# P09_Ethernet.net
KiCad netlist of a schematic drawn in Altium Designer
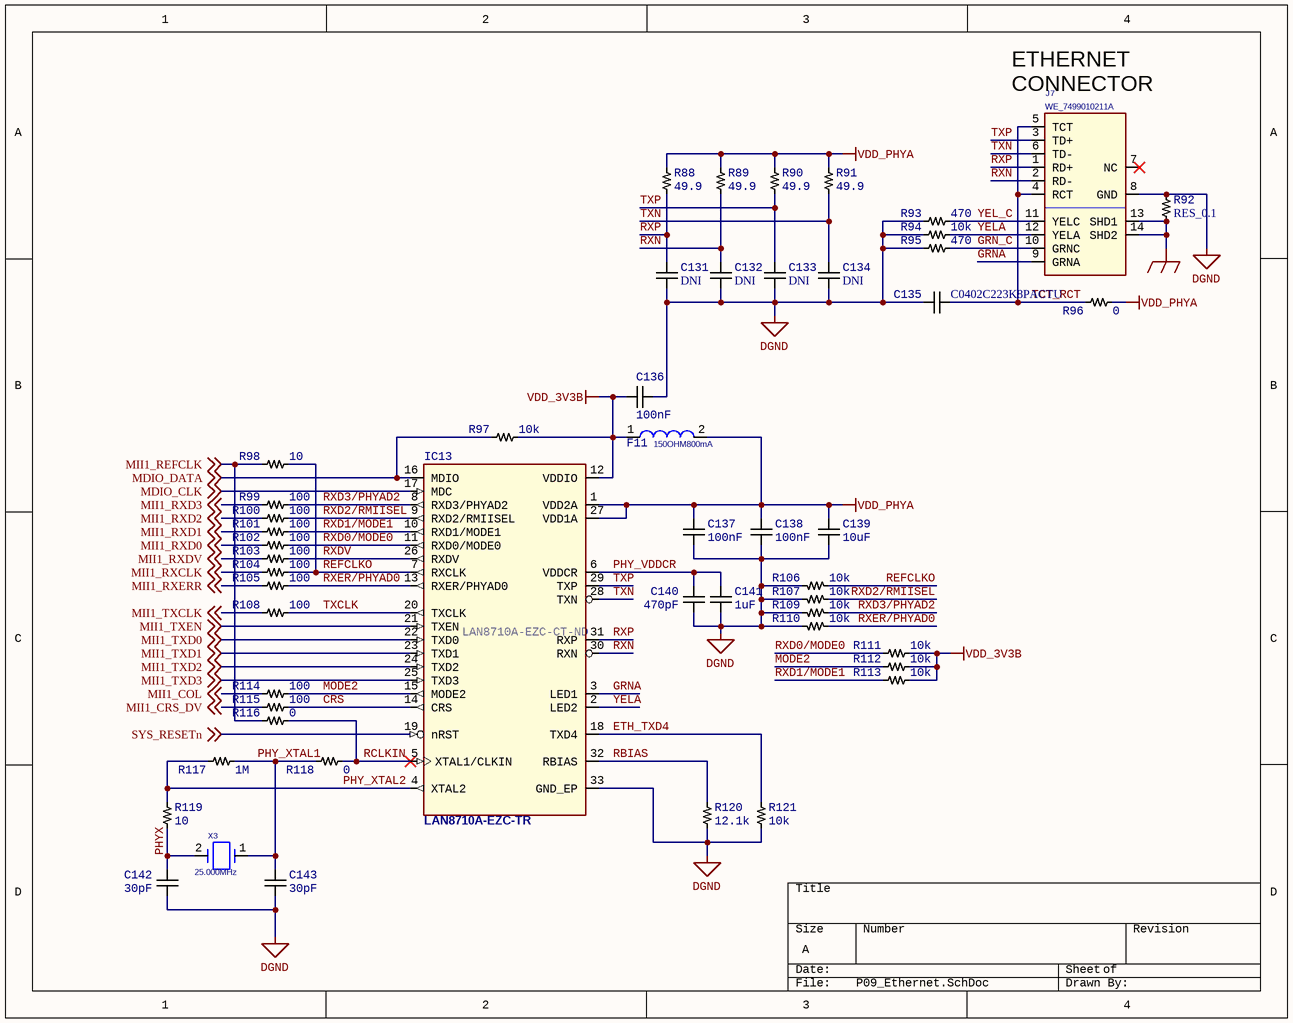
[diagram p0: P09_Ethernet.SchDoc]

(export (version "E")
  (design (tool "Eeschema 10.0.6"))
  (components
    (comp (ref "C131")
      (value "DNI")
      (footprint "Orient:CAP0402_DNI")
      (description "No insert capacitor")
      (libsource (lib "Orient") (part "CAP_15pF_DNI"))
    )
    (comp (ref "C132")
      (value "DNI")
      (footprint "Orient:CAP0402_DNI")
      (description "No insert capacitor")
      (libsource (lib "Orient") (part "CAP_15pF_DNI"))
    )
    (comp (ref "C133")
      (value "DNI")
      (footprint "Orient:CAP0402_DNI")
      (description "No insert capacitor")
      (libsource (lib "Orient") (part "CAP_15pF_DNI"))
    )
    (comp (ref "C134")
      (value "DNI")
      (footprint "Orient:CAP0402_DNI")
      (description "No insert capacitor")
      (libsource (lib "Orient") (part "CAP_15pF_DNI"))
    )
    (comp (ref "C135")
      (value "C0402C223K8PACTU")
      (footprint "Orient:CAP0402")
      (description "MLCC 22nF 0402 SMD")
      (fields (field (name "MANUFACTURER") "KEMET") (field (name "TOLERANCE") "10%"))
      (libsource (lib "Orient") (part "CAP_22nF"))
    )
    (comp (ref "C136")
      (value "C0402C104K4RACTU")
      (footprint "Orient:CAP0402")
      (description "MLCC 100nF 0402 SMD")
      (fields
        (field (name "MANUFACTURER") "KEMET")
        (field (name "CAPACITANCE") "100nF")
        (field (name "TOLERANCE") "10%")
      )
      (libsource (lib "Orient") (part "CAP_100nF"))
    )
    (comp (ref "C137")
      (value "C0402C104K4RACTU")
      (footprint "Orient:CAP0402")
      (description "MLCC 100nF 0402 SMD")
      (fields
        (field (name "MANUFACTURER") "KEMET")
        (field (name "CAPACITANCE") "100nF")
        (field (name "TOLERANCE") "10%")
      )
      (libsource (lib "Orient") (part "CAP_100nF"))
    )
    (comp (ref "C138")
      (value "C0402C104K4RACTU")
      (footprint "Orient:CAP0402")
      (description "MLCC 100nF 0402 SMD")
      (fields
        (field (name "MANUFACTURER") "KEMET")
        (field (name "CAPACITANCE") "100nF")
        (field (name "TOLERANCE") "10%")
      )
      (libsource (lib "Orient") (part "CAP_100nF"))
    )
    (comp (ref "C139")
      (value "10uF")
      (footprint "Orient:CAP0805")
      (description "MLCC 10uF 0805 SMD")
      (fields
        (field (name "MANUFACTURER") "TDK")
        (field (name "MANUFACTURER PART NUMBER") "C2012X6S1A106K085AC")
      )
      (libsource (lib "Orient") (part "CAP_10uF"))
    )
    (comp (ref "C140")
      (value "470pF")
      (footprint "Orient:CAP0402")
      (description "MLCC 470pF 0402 SMD")
      (fields
        (field (name "MANUFACTURER") "Murata")
        (field (name "MANUFACTURER PART NUMBER") "GRM155R71H471KA01D")
      )
      (libsource (lib "Orient") (part "CAP_470pF"))
    )
    (comp (ref "C141")
      (value "1uF")
      (footprint "Orient:CAP0402")
      (description "MLCC 1uF 0402 SMD")
      (fields
        (field (name "MANUFACTURER") "Yageo")
        (field (name "MANUFACTURER PART NUMBER") "CC0402KRX5R6BB105")
      )
      (libsource (lib "Orient") (part "CAP_1uF"))
    )
    (comp (ref "C142")
      (value "CC0402JRNPO9BN300")
      (footprint "Orient:CAP0402")
      (description "MLCC 30pF 0402 SMD")
      (fields
        (field (name "MANUFACTURER") "Yageo")
        (field (name "TOLERANCE") "5%")
        (field (name "CAPACITANCE") "30pF")
      )
      (libsource (lib "Orient") (part "CAP_30pF"))
    )
    (comp (ref "C143")
      (value "CC0402JRNPO9BN300")
      (footprint "Orient:CAP0402")
      (description "MLCC 30pF 0402 SMD")
      (fields
        (field (name "MANUFACTURER") "Yageo")
        (field (name "TOLERANCE") "5%")
        (field (name "CAPACITANCE") "30pF")
      )
      (libsource (lib "Orient") (part "CAP_30pF"))
    )
    (comp (ref "F11")
      (value "150OHM800mA")
      (footprint "Orient:FB0805")
      (description "FERRITE 800MA 150 OHM 0805 SMD")
      (fields (field (name "MFR") "Steward") (field (name "TIINTPARTNUMBER") "1L0010"))
      (libsource (lib "Orient") (part "FERR"))
    )
    (comp (ref "IC13")
      (value "LAN8710A-EZC-TR")
      (footprint "Orient:QFN-32")
      (description "Ethernet ICs 10/100 Ethernet XCVR w/HPAutoMDIX FlexPwr")
      (fields
        (field (name "PART#") "SMSC LAN8710A-EZK")
        (field (name "MANUFACTURER") "Microchip Technology")
        (field (name "SUPPLIER PART NUMBER 2") "LAN8710A-EZC-CT-ND")
      )
      (libsource (lib "Orient") (part "IC_Ethernet_XCVR"))
    )
    (comp (ref "J7")
      (value "WE_7499010211A")
      (description "WE-RJ45 LAN Transformer")
      (libsource (lib "Orient") (part "CONN_RJ45_MAG_WE_0"))
    )
    (comp (ref "R88")
      (value "RC0402FR-0749R9")
      (footprint "Orient:RES0402")
      (description "Resistor 49.9Ohm 0402 SMD")
      (fields
        (field (name "MANUFACTURER") "Yageo")
        (field (name "MANUFACTURER PART NUMBER") "RC0402FR-0749R9L")
        (field (name "RESISTANCE") "49.9")
      )
      (libsource (lib "Orient") (part "RES_49.9"))
    )
    (comp (ref "R89")
      (value "RC0402FR-0749R9")
      (footprint "Orient:RES0402")
      (description "Resistor 49.9Ohm 0402 SMD")
      (fields
        (field (name "MANUFACTURER") "Yageo")
        (field (name "MANUFACTURER PART NUMBER") "RC0402FR-0749R9L")
        (field (name "RESISTANCE") "49.9")
      )
      (libsource (lib "Orient") (part "RES_49.9"))
    )
    (comp (ref "R90")
      (value "RC0402FR-0749R9")
      (footprint "Orient:RES0402")
      (description "Resistor 49.9Ohm 0402 SMD")
      (fields
        (field (name "MANUFACTURER") "Yageo")
        (field (name "MANUFACTURER PART NUMBER") "RC0402FR-0749R9L")
        (field (name "RESISTANCE") "49.9")
      )
      (libsource (lib "Orient") (part "RES_49.9"))
    )
    (comp (ref "R91")
      (value "RC0402FR-0749R9")
      (footprint "Orient:RES0402")
      (description "Resistor 49.9Ohm 0402 SMD")
      (fields
        (field (name "MANUFACTURER") "Yageo")
        (field (name "MANUFACTURER PART NUMBER") "RC0402FR-0749R9L")
        (field (name "RESISTANCE") "49.9")
      )
      (libsource (lib "Orient") (part "RES_49.9"))
    )
    (comp (ref "R92")
      (value "RES_0.1")
      (description "Resistor 0.1Ohm 0805 SMD")
      (libsource (lib "Orient") (part "RES_0.1"))
    )
    (comp (ref "R93")
      (value "RC0402FR-07470RL")
      (footprint "Orient:RES0402")
      (description "Resistor 470Ohm 0402 SMD")
      (fields
        (field (name "MANUFACTURER") "Yageo Phycomp")
        (field (name "TOLERANCE") "1%")
        (field (name "RESISTANCE") "470")
      )
      (libsource (lib "Orient") (part "RES_470"))
    )
    (comp (ref "R94")
      (value "RC0402FR-0710KL")
      (footprint "Orient:RES0402")
      (description "Resistor 10kOhm 0402 SMD")
      (fields
        (field (name "MANUFACTURER") "Yageo")
        (field (name "TOLERANCE") "1%")
        (field (name "RESISTANCE") "10k")
      )
      (libsource (lib "Orient") (part "RES_10k"))
    )
    (comp (ref "R95")
      (value "RC0402FR-07470RL")
      (footprint "Orient:RES0402")
      (description "Resistor 470Ohm 0402 SMD")
      (fields
        (field (name "MANUFACTURER") "Yageo Phycomp")
        (field (name "TOLERANCE") "1%")
        (field (name "RESISTANCE") "470")
      )
      (libsource (lib "Orient") (part "RES_470"))
    )
    (comp (ref "R96")
      (value "RC0402JR-070RL")
      (footprint "Orient:RES0402")
      (description "Resistor 0Ohm 0402 SMD")
      (fields
        (field (name "MANUFACTURER") "Yageo")
        (field (name "TOLERANCE") "5%")
        (field (name "RESISTANCE") "0")
      )
      (libsource (lib "Orient") (part "RES_0"))
    )
    (comp (ref "R97")
      (value "RC0402FR-0710KL")
      (footprint "Orient:RES0402")
      (description "Resistor 10kOhm 0402 SMD")
      (fields
        (field (name "MANUFACTURER") "Yageo")
        (field (name "TOLERANCE") "1%")
        (field (name "RESISTANCE") "10k")
      )
      (libsource (lib "Orient") (part "RES_10k"))
    )
    (comp (ref "R98")
      (value "RC0402FR-0710RL")
      (footprint "Orient:RES0402")
      (description "Resistor 10Ohm 0402 SMD")
      (fields
        (field (name "MANUFACTURER") "Yageo")
        (field (name "TOLERANCE") "1%")
        (field (name "RESISTANCE") "10")
      )
      (libsource (lib "Orient") (part "RES_10"))
    )
    (comp (ref "R99")
      (value "RC0402FR-07100RL")
      (footprint "Orient:RES0402")
      (description "Resistor 100Ohm 0402 SMD")
      (fields
        (field (name "MANUFACTURER") "Yageo")
        (field (name "TOLERANCE") "1%")
        (field (name "RESISTANCE") "100")
      )
      (libsource (lib "Orient") (part "RES_100"))
    )
    (comp (ref "R100")
      (value "RC0402FR-07100RL")
      (footprint "Orient:RES0402")
      (description "Resistor 100Ohm 0402 SMD")
      (fields
        (field (name "MANUFACTURER") "Yageo")
        (field (name "TOLERANCE") "1%")
        (field (name "RESISTANCE") "100")
      )
      (libsource (lib "Orient") (part "RES_100"))
    )
    (comp (ref "R101")
      (value "RC0402FR-07100RL")
      (footprint "Orient:RES0402")
      (description "Resistor 100Ohm 0402 SMD")
      (fields
        (field (name "MANUFACTURER") "Yageo")
        (field (name "TOLERANCE") "1%")
        (field (name "RESISTANCE") "100")
      )
      (libsource (lib "Orient") (part "RES_100"))
    )
    (comp (ref "R102")
      (value "RC0402FR-07100RL")
      (footprint "Orient:RES0402")
      (description "Resistor 100Ohm 0402 SMD")
      (fields
        (field (name "MANUFACTURER") "Yageo")
        (field (name "TOLERANCE") "1%")
        (field (name "RESISTANCE") "100")
      )
      (libsource (lib "Orient") (part "RES_100"))
    )
    (comp (ref "R103")
      (value "RC0402FR-07100RL")
      (footprint "Orient:RES0402")
      (description "Resistor 100Ohm 0402 SMD")
      (fields
        (field (name "MANUFACTURER") "Yageo")
        (field (name "TOLERANCE") "1%")
        (field (name "RESISTANCE") "100")
      )
      (libsource (lib "Orient") (part "RES_100"))
    )
    (comp (ref "R104")
      (value "RC0402FR-07100RL")
      (footprint "Orient:RES0402")
      (description "Resistor 100Ohm 0402 SMD")
      (fields
        (field (name "MANUFACTURER") "Yageo")
        (field (name "TOLERANCE") "1%")
        (field (name "RESISTANCE") "100")
      )
      (libsource (lib "Orient") (part "RES_100"))
    )
    (comp (ref "R105")
      (value "RC0402FR-07100RL")
      (footprint "Orient:RES0402")
      (description "Resistor 100Ohm 0402 SMD")
      (fields
        (field (name "MANUFACTURER") "Yageo")
        (field (name "TOLERANCE") "1%")
        (field (name "RESISTANCE") "100")
      )
      (libsource (lib "Orient") (part "RES_100"))
    )
    (comp (ref "R106")
      (value "RC0402FR-0710KL")
      (footprint "Orient:RES0402")
      (description "Resistor 10kOhm 0402 SMD")
      (fields
        (field (name "MANUFACTURER") "Yageo")
        (field (name "TOLERANCE") "1%")
        (field (name "RESISTANCE") "10k")
      )
      (libsource (lib "Orient") (part "RES_10k"))
    )
    (comp (ref "R107")
      (value "RC0402FR-0710KL")
      (footprint "Orient:RES0402")
      (description "Resistor 10kOhm 0402 SMD")
      (fields
        (field (name "MANUFACTURER") "Yageo")
        (field (name "TOLERANCE") "1%")
        (field (name "RESISTANCE") "10k")
      )
      (libsource (lib "Orient") (part "RES_10k"))
    )
    (comp (ref "R108")
      (value "RC0402FR-07100RL")
      (footprint "Orient:RES0402")
      (description "Resistor 100Ohm 0402 SMD")
      (fields
        (field (name "TOLERANCE") "1%")
        (field (name "MANUFACTURER") "Yageo")
        (field (name "RESISTANCE") "100")
      )
      (libsource (lib "Orient") (part "RES_100"))
    )
    (comp (ref "R109")
      (value "RC0402FR-0710KL")
      (footprint "Orient:RES0402")
      (description "Resistor 10kOhm 0402 SMD")
      (fields
        (field (name "MANUFACTURER") "Yageo")
        (field (name "TOLERANCE") "1%")
        (field (name "RESISTANCE") "10k")
      )
      (libsource (lib "Orient") (part "RES_10k"))
    )
    (comp (ref "R110")
      (value "RC0402FR-0710KL")
      (footprint "Orient:RES0402")
      (description "Resistor 10kOhm 0402 SMD")
      (fields
        (field (name "MANUFACTURER") "Yageo")
        (field (name "TOLERANCE") "1%")
        (field (name "RESISTANCE") "10k")
      )
      (libsource (lib "Orient") (part "RES_10k"))
    )
    (comp (ref "R111")
      (value "RC0402FR-0710KL")
      (footprint "Orient:RES0402")
      (description "Resistor 10kOhm 0402 SMD")
      (fields
        (field (name "MANUFACTURER") "Yageo")
        (field (name "TOLERANCE") "1%")
        (field (name "RESISTANCE") "10k")
      )
      (libsource (lib "Orient") (part "RES_10k"))
    )
    (comp (ref "R112")
      (value "RC0402FR-0710KL")
      (footprint "Orient:RES0402")
      (description "Resistor 10kOhm 0402 SMD")
      (fields
        (field (name "MANUFACTURER") "Yageo")
        (field (name "TOLERANCE") "1%")
        (field (name "RESISTANCE") "10k")
      )
      (libsource (lib "Orient") (part "RES_10k"))
    )
    (comp (ref "R113")
      (value "RC0402FR-0710KL")
      (footprint "Orient:RES0402")
      (description "Resistor 10kOhm 0402 SMD")
      (fields
        (field (name "MANUFACTURER") "Yageo")
        (field (name "TOLERANCE") "1%")
        (field (name "RESISTANCE") "10k")
      )
      (libsource (lib "Orient") (part "RES_10k"))
    )
    (comp (ref "R114")
      (value "RC0402FR-07100RL")
      (footprint "Orient:RES0402")
      (description "Resistor 100Ohm 0402 SMD")
      (fields
        (field (name "TOLERANCE") "1%")
        (field (name "MANUFACTURER") "Yageo")
        (field (name "RESISTANCE") "100")
      )
      (libsource (lib "Orient") (part "RES_100"))
    )
    (comp (ref "R115")
      (value "RC0402FR-07100RL")
      (footprint "Orient:RES0402")
      (description "Resistor 100Ohm 0402 SMD")
      (fields
        (field (name "MANUFACTURER") "Yageo")
        (field (name "TOLERANCE") "1%")
        (field (name "RESISTANCE") "100")
      )
      (libsource (lib "Orient") (part "RES_100"))
    )
    (comp (ref "R116")
      (value "RC0402JR-070RL")
      (footprint "Orient:RES0402")
      (description "Resistor 0Ohm 0402 SMD")
      (fields
        (field (name "MANUFACTURER") "Yageo")
        (field (name "TOLERANCE") "5%")
        (field (name "RESISTANCE") "0")
      )
      (libsource (lib "Orient") (part "RES_0"))
    )
    (comp (ref "R117")
      (value "RC0402FR-071ML")
      (footprint "Orient:RES0402")
      (description "Resistor 1MOhm 0402 SMD")
      (fields
        (field (name "MANUFACTURER") "Yageo")
        (field (name "TOLERANCE") "1%")
        (field (name "RESISTANCE") "1M")
      )
      (libsource (lib "Orient") (part "RES_1M"))
    )
    (comp (ref "R118")
      (value "RC0402JR-070RL")
      (footprint "Orient:RES0402")
      (description "Resistor 0Ohm 0402 SMD")
      (fields
        (field (name "MANUFACTURER") "Yageo")
        (field (name "TOLERANCE") "5%")
        (field (name "RESISTANCE") "0")
      )
      (libsource (lib "Orient") (part "RES_0"))
    )
    (comp (ref "R119")
      (value "RC0402FR-0710RL")
      (footprint "Orient:RES0402")
      (description "Resistor 10Ohm 0402 SMD")
      (fields
        (field (name "MANUFACTURER") "Yageo")
        (field (name "TOLERANCE") "1%")
        (field (name "RESISTANCE") "10")
      )
      (libsource (lib "Orient") (part "RES_10"))
    )
    (comp (ref "R120")
      (value "RC0402FR-0712K1L")
      (footprint "Orient:RES0402")
      (description "Resistor 12.1kOhm 0402 SMD")
      (fields
        (field (name "MANUFACTURER") "Yageo")
        (field (name "TOLERANCE") "1%")
        (field (name "RESISTANCE") "12.1k")
      )
      (libsource (lib "Orient") (part "RES_12.1k"))
    )
    (comp (ref "R121")
      (value "RC0402FR-0710KL")
      (footprint "Orient:RES0402")
      (description "Resistor 10kOhm 0402 SMD")
      (fields
        (field (name "MANUFACTURER") "Yageo")
        (field (name "TOLERANCE") "1%")
        (field (name "RESISTANCE") "10k")
      )
      (libsource (lib "Orient") (part "RES_10k"))
    )
    (comp (ref "X3")
      (value "25.000MHz")
      (footprint "Orient:XTAL150SMD_125X196")
      (fields
        (field (name "MANUFACTURER") "Abracon Corporation")
        (field (name "MANUFACTURER PART NUMBER") "ABM3-25.000MHZ-B2-T")
      )
      (libsource (lib "Orient") (part "Suntsu ITEMP 25MHz _0.005% 20pf"))
    )
  )
  (nets
    (net (code "1") (name "/CRS") (class "Default")
      (node (ref "IC13") (pin "14") (pinfunction "CRS_14") (pintype "output"))
      (node (ref "R115") (pin "1") (pintype "passive"))
    )
    (net (code "2") (name "/ETH_TXD4") (class "Default")
      (node (ref "IC13") (pin "18") (pinfunction "TXD4_18") (pintype "bidirectional"))
      (node (ref "R121") (pin "2") (pintype "passive"))
    )
    (net (code "3") (name "/GRNA") (class "Default")
      (node (ref "IC13") (pin "3") (pinfunction "LED1_3") (pintype "bidirectional"))
      (node (ref "J7") (pin "9") (pinfunction "GRNA_9") (pintype "passive"))
    )
    (net (code "4") (name "/GRN_C") (class "Default")
      (node (ref "J7") (pin "10") (pinfunction "GRNC_10") (pintype "passive"))
      (node (ref "R95") (pin "1") (pintype "passive"))
    )
    (net (code "5") (name "/MODE2") (class "Default")
      (node (ref "IC13") (pin "15") (pinfunction "MODE2_15") (pintype "output"))
      (node (ref "R112") (pin "1") (pintype "passive"))
      (node (ref "R114") (pin "1") (pintype "passive"))
    )
    (net (code "6") (name "/PHYX") (class "Default")
      (node (ref "C142") (pin "1") (pintype "passive"))
      (node (ref "R119") (pin "1") (pintype "passive"))
      (node (ref "X3") (pin "2") (pinfunction "2_2") (pintype "passive"))
    )
    (net (code "7") (name "/PHY_VDDCR") (class "Default")
      (node (ref "C140") (pin "1") (pintype "passive"))
      (node (ref "C141") (pin "1") (pintype "passive"))
      (node (ref "IC13") (pin "6") (pinfunction "VDDCR_6") (pintype "power_in"))
    )
    (net (code "8") (name "/PHY_XTAL1") (class "Default")
      (node (ref "C143") (pin "1") (pintype "passive"))
      (node (ref "R117") (pin "1") (pintype "passive"))
      (node (ref "R118") (pin "2") (pintype "passive"))
      (node (ref "X3") (pin "1") (pinfunction "1_1") (pintype "passive"))
    )
    (net (code "9") (name "/PHY_XTAL2") (class "Default")
      (node (ref "IC13") (pin "4") (pinfunction "XTAL2_4") (pintype "output"))
      (node (ref "R117") (pin "2") (pintype "passive"))
      (node (ref "R119") (pin "2") (pintype "passive"))
    )
    (net (code "10") (name "/RBIAS") (class "Default")
      (node (ref "IC13") (pin "32") (pinfunction "RBIAS_32") (pintype "passive"))
      (node (ref "R120") (pin "2") (pintype "passive"))
    )
    (net (code "11") (name "/RCLKIN") (class "Default")
      (node (ref "IC13") (pin "5") (pinfunction "XTAL1/CLKIN_5") (pintype "input"))
      (node (ref "R116") (pin "1") (pintype "passive"))
      (node (ref "R118") (pin "1") (pintype "passive"))
    )
    (net (code "12") (name "/REFCLKO") (class "Default")
      (node (ref "IC13") (pin "7") (pinfunction "RXCLK_7") (pintype "output"))
      (node (ref "R104") (pin "1") (pintype "passive"))
      (node (ref "R106") (pin "1") (pintype "passive"))
      (node (ref "R98") (pin "1") (pintype "passive"))
    )
    (net (code "13") (name "/RXD0{slash}MODE0") (class "Default")
      (node (ref "IC13") (pin "11") (pinfunction "RXD0/MODE0_11") (pintype "output"))
      (node (ref "R102") (pin "1") (pintype "passive"))
      (node (ref "R111") (pin "1") (pintype "passive"))
    )
    (net (code "14") (name "/RXD1{slash}MODE1") (class "Default")
      (node (ref "IC13") (pin "10") (pinfunction "RXD1/MODE1_10") (pintype "output"))
      (node (ref "R101") (pin "1") (pintype "passive"))
      (node (ref "R113") (pin "1") (pintype "passive"))
    )
    (net (code "15") (name "/RXD2{slash}RMIISEL") (class "Default")
      (node (ref "IC13") (pin "9") (pinfunction "RXD2/RMIISEL_9") (pintype "output"))
      (node (ref "R100") (pin "1") (pintype "passive"))
      (node (ref "R107") (pin "1") (pintype "passive"))
    )
    (net (code "16") (name "/RXD3{slash}PHYAD2") (class "Default")
      (node (ref "IC13") (pin "8") (pinfunction "RXD3/PHYAD2_8") (pintype "output"))
      (node (ref "R109") (pin "1") (pintype "passive"))
      (node (ref "R99") (pin "1") (pintype "passive"))
    )
    (net (code "17") (name "/RXDV") (class "Default")
      (node (ref "IC13") (pin "26") (pinfunction "RXDV_26") (pintype "output"))
      (node (ref "R103") (pin "1") (pintype "passive"))
    )
    (net (code "18") (name "/RXER{slash}PHYAD0") (class "Default")
      (node (ref "IC13") (pin "13") (pinfunction "RXER/PHYAD0_13") (pintype "output"))
      (node (ref "R105") (pin "1") (pintype "passive"))
      (node (ref "R110") (pin "1") (pintype "passive"))
    )
    (net (code "19") (name "/RXN") (class "Default")
      (node (ref "C132") (pin "1") (pintype "passive"))
      (node (ref "IC13") (pin "30") (pinfunction "RXN_30") (pintype "bidirectional"))
      (node (ref "J7") (pin "2") (pinfunction "RD-_2") (pintype "passive"))
      (node (ref "R89") (pin "2") (pintype "passive"))
    )
    (net (code "20") (name "/RXP") (class "Default")
      (node (ref "C131") (pin "1") (pintype "passive"))
      (node (ref "IC13") (pin "31") (pinfunction "RXP_31") (pintype "bidirectional"))
      (node (ref "J7") (pin "1") (pinfunction "RD+_1") (pintype "passive"))
      (node (ref "R88") (pin "2") (pintype "passive"))
    )
    (net (code "21") (name "/TCT_RCT") (class "Default")
      (node (ref "C135") (pin "2") (pintype "passive"))
      (node (ref "J7") (pin "4") (pinfunction "RCT_4") (pintype "passive"))
      (node (ref "J7") (pin "5") (pinfunction "TCT_5") (pintype "passive"))
      (node (ref "R96") (pin "2") (pintype "passive"))
    )
    (net (code "22") (name "/TXCLK") (class "Default")
      (node (ref "IC13") (pin "20") (pinfunction "TXCLK_20") (pintype "output"))
      (node (ref "R108") (pin "1") (pintype "passive"))
    )
    (net (code "23") (name "/TXN") (class "Default")
      (node (ref "C134") (pin "1") (pintype "passive"))
      (node (ref "IC13") (pin "28") (pinfunction "TXN_28") (pintype "bidirectional"))
      (node (ref "J7") (pin "6") (pinfunction "TD-_6") (pintype "passive"))
      (node (ref "R91") (pin "2") (pintype "passive"))
    )
    (net (code "24") (name "/TXP") (class "Default")
      (node (ref "C133") (pin "1") (pintype "passive"))
      (node (ref "IC13") (pin "29") (pinfunction "TXP_29") (pintype "bidirectional"))
      (node (ref "J7") (pin "3") (pinfunction "TD+_3") (pintype "passive"))
      (node (ref "R90") (pin "2") (pintype "passive"))
    )
    (net (code "25") (name "/YELA") (class "Default")
      (node (ref "IC13") (pin "2") (pinfunction "LED2_2") (pintype "bidirectional"))
      (node (ref "J7") (pin "12") (pinfunction "YELA_12") (pintype "passive"))
      (node (ref "R94") (pin "1") (pintype "passive"))
    )
    (net (code "26") (name "/YEL_C") (class "Default")
      (node (ref "J7") (pin "11") (pinfunction "YELC_11") (pintype "passive"))
      (node (ref "R93") (pin "1") (pintype "passive"))
    )
    (net (code "27") (name "DGND") (class "Default")
      (node (ref "C131") (pin "2") (pintype "passive"))
      (node (ref "C132") (pin "2") (pintype "passive"))
      (node (ref "C133") (pin "2") (pintype "passive"))
      (node (ref "C134") (pin "2") (pintype "passive"))
      (node (ref "C135") (pin "1") (pintype "passive"))
      (node (ref "C136") (pin "2") (pintype "passive"))
      (node (ref "C137") (pin "2") (pintype "passive"))
      (node (ref "C138") (pin "2") (pintype "passive"))
      (node (ref "C139") (pin "1") (pintype "passive"))
      (node (ref "C140") (pin "2") (pintype "passive"))
      (node (ref "C141") (pin "2") (pintype "passive"))
      (node (ref "C142") (pin "2") (pintype "passive"))
      (node (ref "C143") (pin "2") (pintype "passive"))
      (node (ref "IC13") (pin "33") (pinfunction "GND_EP_33") (pintype "power_in"))
      (node (ref "J7") (pin "8") (pinfunction "GND_8") (pintype "passive"))
      (node (ref "R106") (pin "2") (pintype "passive"))
      (node (ref "R107") (pin "2") (pintype "passive"))
      (node (ref "R109") (pin "2") (pintype "passive"))
      (node (ref "R110") (pin "2") (pintype "passive"))
      (node (ref "R120") (pin "1") (pintype "passive"))
      (node (ref "R121") (pin "1") (pintype "passive"))
      (node (ref "R92") (pin "2") (pintype "passive"))
      (node (ref "R93") (pin "2") (pintype "passive"))
      (node (ref "R94") (pin "2") (pintype "passive"))
      (node (ref "R95") (pin "2") (pintype "passive"))
    )
    (net (code "28") (name "GND_EARTH") (class "Default")
      (node (ref "J7") (pin "13") (pinfunction "SHD1_13") (pintype "passive"))
      (node (ref "J7") (pin "14") (pinfunction "SHD2_14") (pintype "passive"))
      (node (ref "R92") (pin "1") (pintype "passive"))
    )
    (net (code "29") (name "MDIO_CLK") (class "Default")
      (node (ref "IC13") (pin "17") (pinfunction "MDC_17") (pintype "input"))
    )
    (net (code "30") (name "MDIO_DATA") (class "Default")
      (node (ref "IC13") (pin "16") (pinfunction "MDIO_16") (pintype "bidirectional"))
      (node (ref "R97") (pin "2") (pintype "passive"))
    )
    (net (code "31") (name "MII1_COL") (class "Default") (node (ref "R114") (pin "2") (pintype "passive")))
    (net (code "32") (name "MII1_CRS_DV") (class "Default") (node (ref "R115") (pin "2") (pintype "passive")))
    (net (code "33") (name "MII1_REFCLK") (class "Default")
      (node (ref "R116") (pin "2") (pintype "passive"))
      (node (ref "R98") (pin "2") (pintype "passive"))
    )
    (net (code "34") (name "MII1_RXCLK") (class "Default") (node (ref "R104") (pin "2") (pintype "passive")))
    (net (code "35") (name "MII1_RXD0") (class "Default") (node (ref "R102") (pin "2") (pintype "passive")))
    (net (code "36") (name "MII1_RXD1") (class "Default") (node (ref "R101") (pin "2") (pintype "passive")))
    (net (code "37") (name "MII1_RXD2") (class "Default") (node (ref "R100") (pin "2") (pintype "passive")))
    (net (code "38") (name "MII1_RXD3") (class "Default") (node (ref "R99") (pin "2") (pintype "passive")))
    (net (code "39") (name "MII1_RXDV") (class "Default") (node (ref "R103") (pin "2") (pintype "passive")))
    (net (code "40") (name "MII1_RXERR") (class "Default") (node (ref "R105") (pin "2") (pintype "passive")))
    (net (code "41") (name "MII1_TXCLK") (class "Default") (node (ref "R108") (pin "2") (pintype "passive")))
    (net (code "42") (name "MII1_TXD0") (class "Default")
      (node (ref "IC13") (pin "22") (pinfunction "TXD0_22") (pintype "input"))
    )
    (net (code "43") (name "MII1_TXD1") (class "Default")
      (node (ref "IC13") (pin "23") (pinfunction "TXD1_23") (pintype "input"))
    )
    (net (code "44") (name "MII1_TXD2") (class "Default")
      (node (ref "IC13") (pin "24") (pinfunction "TXD2_24") (pintype "input"))
    )
    (net (code "45") (name "MII1_TXD3") (class "Default")
      (node (ref "IC13") (pin "25") (pinfunction "TXD3_25") (pintype "input"))
    )
    (net (code "46") (name "MII1_TXEN") (class "Default")
      (node (ref "IC13") (pin "21") (pinfunction "TXEN_21") (pintype "input"))
    )
    (net (code "47") (name "SYS_RESETn") (class "Default")
      (node (ref "IC13") (pin "19") (pinfunction "nRST_19") (pintype "input"))
    )
    (net (code "48") (name "VDD_3V3B") (class "Default")
      (node (ref "C136") (pin "1") (pintype "passive"))
      (node (ref "F11") (pin "1") (pinfunction "1_1") (pintype "passive"))
      (node (ref "IC13") (pin "12") (pinfunction "VDDIO_12") (pintype "power_in"))
      (node (ref "R111") (pin "2") (pintype "passive"))
      (node (ref "R112") (pin "2") (pintype "passive"))
      (node (ref "R113") (pin "2") (pintype "passive"))
      (node (ref "R97") (pin "1") (pintype "passive"))
    )
    (net (code "49") (name "VDD_PHYA") (class "Default")
      (node (ref "C137") (pin "1") (pintype "passive"))
      (node (ref "C138") (pin "1") (pintype "passive"))
      (node (ref "C139") (pin "2") (pintype "passive"))
      (node (ref "F11") (pin "2") (pinfunction "2_2") (pintype "passive"))
      (node (ref "IC13") (pin "1") (pinfunction "VDD2A_1") (pintype "power_in"))
      (node (ref "IC13") (pin "27") (pinfunction "VDD1A_27") (pintype "power_in"))
      (node (ref "R88") (pin "1") (pintype "passive"))
      (node (ref "R89") (pin "1") (pintype "passive"))
      (node (ref "R90") (pin "1") (pintype "passive"))
      (node (ref "R91") (pin "1") (pintype "passive"))
      (node (ref "R96") (pin "1") (pintype "passive"))
    )
    (net (code "50") (name "unconnected-(J7-NC-Pad7)") (class "Default")
      (node (ref "J7") (pin "7") (pinfunction "NC_7") (pintype "passive+no_connect"))
    )
  )
)
